# Sheet1.net
KiCad netlist of a schematic drawn in Altium Designer
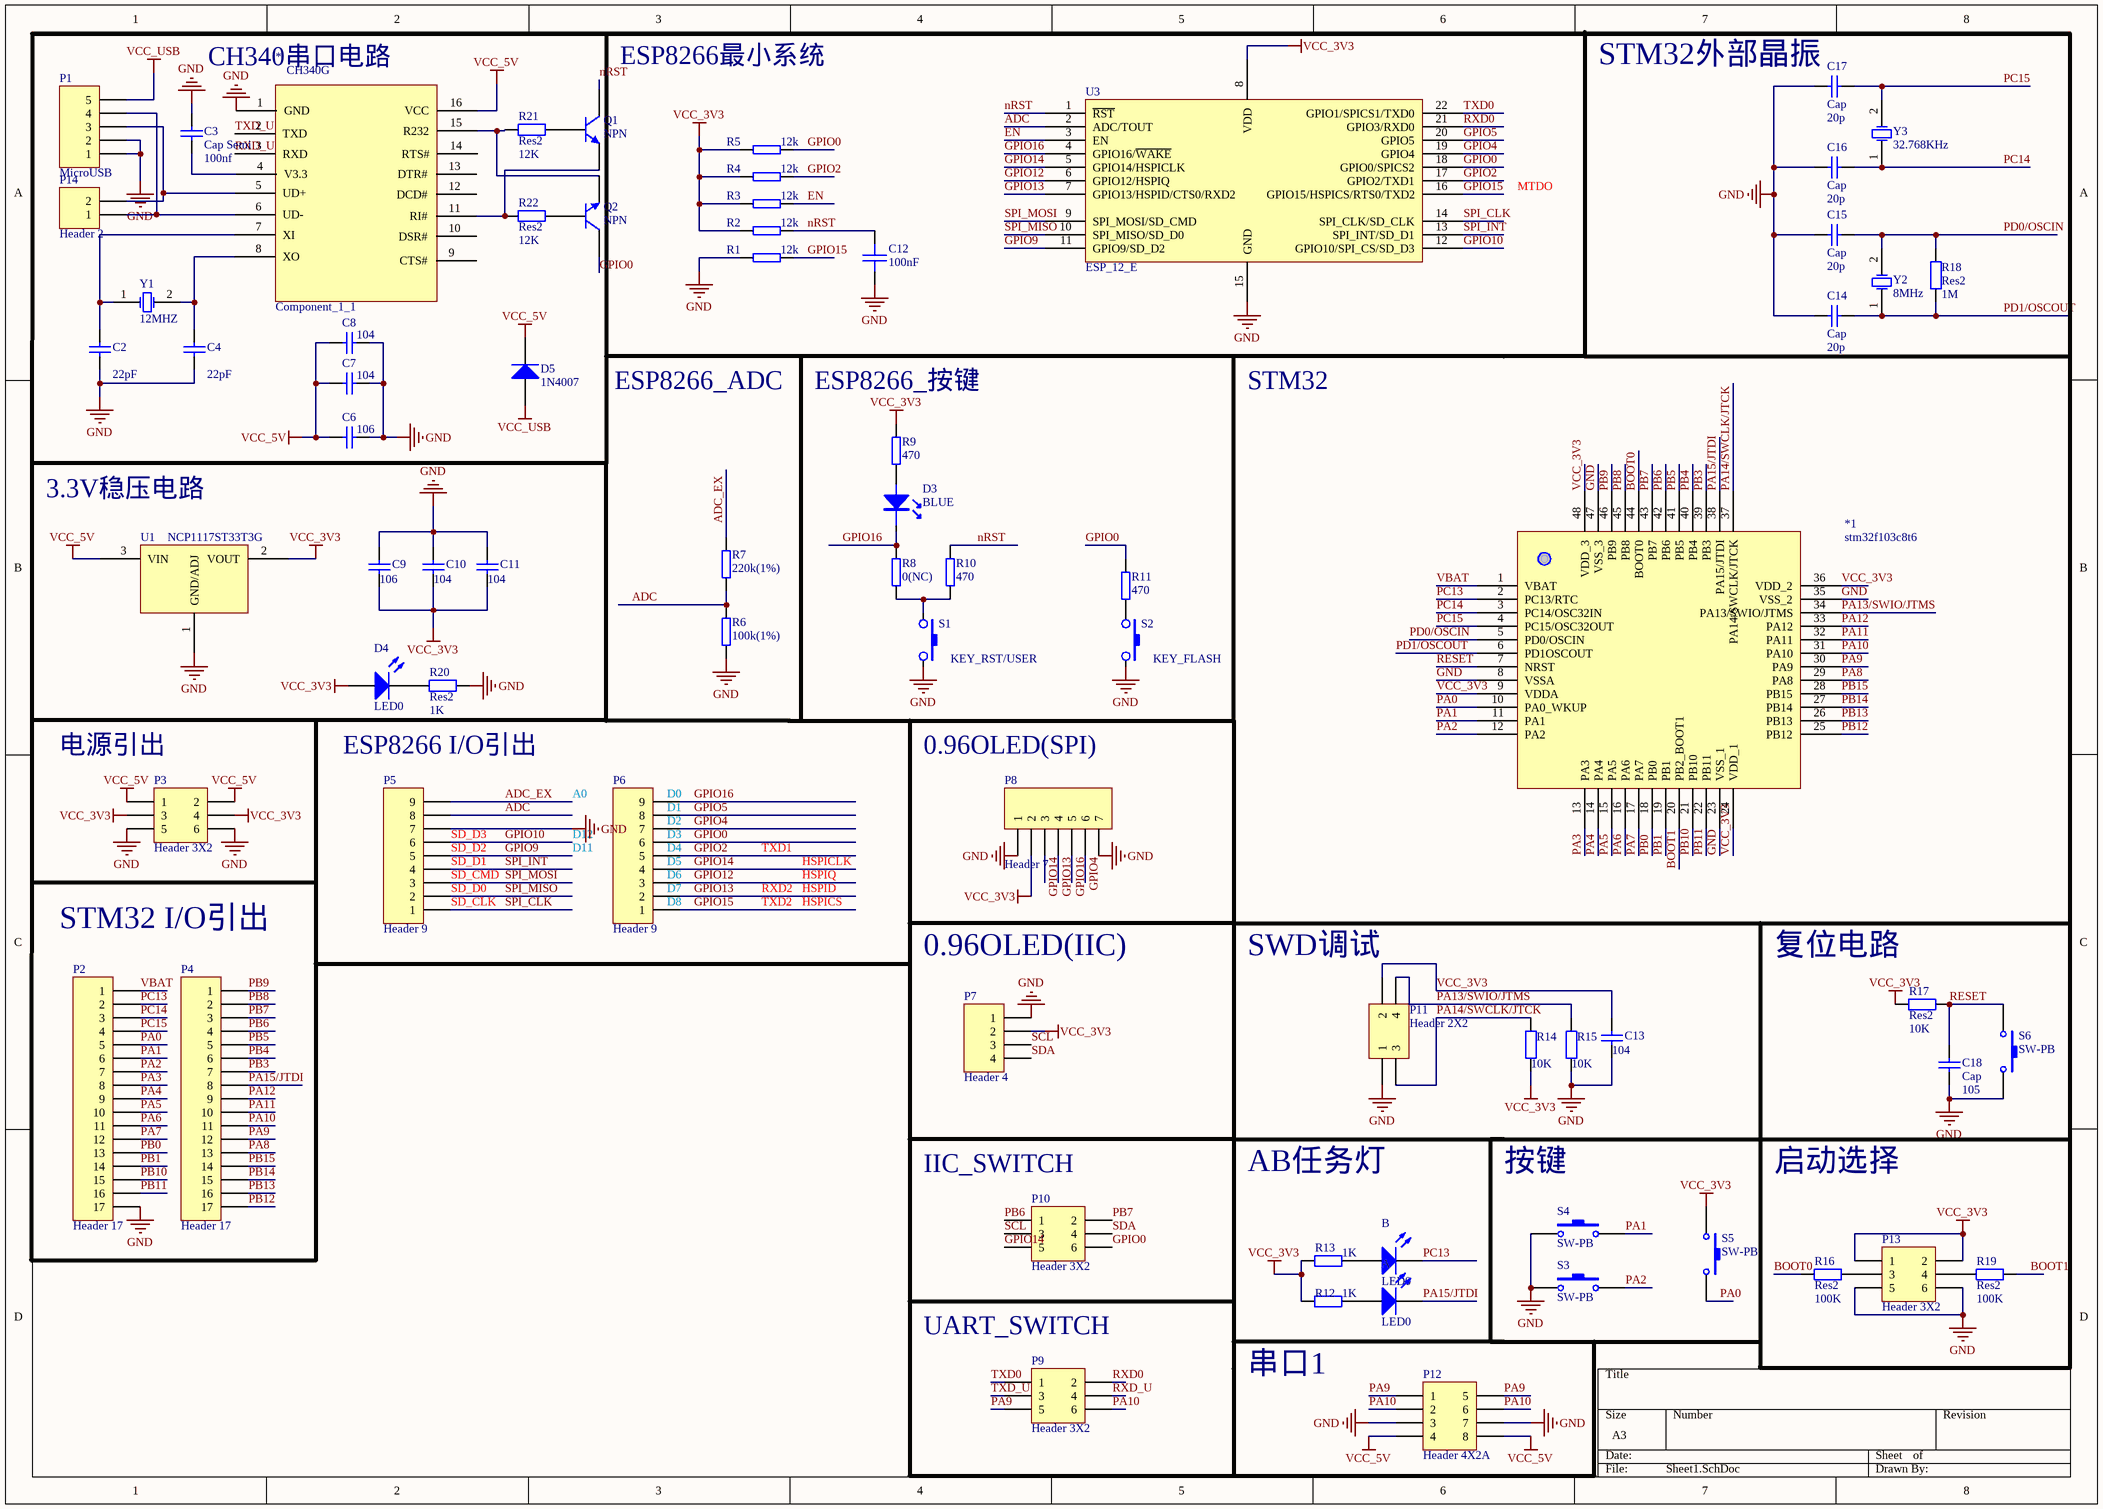
[diagram p0: Sheet1.SchDoc]

(export (version "E")
  (design (tool "Eeschema 10.0.6"))
  (components
    (comp (ref "*") (value "Component_1_1") (libsource (lib "CH340G") (part "Component_1_1")))
    (comp (ref "*1")
      (value "stm32f103c8t6")
      (footprint "LQFP-48_M")
      (libsource (lib "YL_Board") (part "stm32f103c8t6"))
    )
    (comp (ref "A")
      (value "LED0")
      (footprint "2012[0805]")
      (description "Typical INFRARED GaAs LED")
      (fields (field (name "PUBLISHER") "Altium Limited"))
      (libsource (lib "Miscellaneous Devices") (part "LED0"))
    )
    (comp (ref "B")
      (value "LED0")
      (footprint "2012[0805]")
      (description "Typical INFRARED GaAs LED")
      (fields (field (name "PUBLISHER") "Altium Limited"))
      (libsource (lib "Miscellaneous Devices") (part "LED0"))
    )
    (comp (ref "C2")
      (value "22pF")
      (footprint "2012[0805]")
      (description "Capacitor")
      (fields (field (name "Comment") "Cap") (field (name "PUBLISHER") "Altium Limited"))
      (libsource (lib "Miscellaneous Devices") (part "Cap"))
    )
    (comp (ref "C3")
      (value "Cap Semi")
      (footprint "2012[0805]")
      (description "Capacitor (Semiconductor SIM Model)")
      (fields (field (name "ALTIUM_VALUE") "100nf") (field (name "PUBLISHER") "Altium Limited"))
      (libsource (lib "Miscellaneous Devices") (part "Cap Semi"))
    )
    (comp (ref "C4")
      (value "22pF")
      (footprint "2012[0805]")
      (description "Capacitor")
      (fields (field (name "Comment") "Cap") (field (name "PUBLISHER") "Altium Limited"))
      (libsource (lib "Miscellaneous Devices") (part "Cap"))
    )
    (comp (ref "C6")
      (value "106")
      (footprint "C1206")
      (description "Capacitor (Semiconductor SIM Model)")
      (fields (field (name "Comment") "Cap Semi") (field (name "PUBLISHER") "Altium Limited"))
      (libsource (lib "Miscellaneous Devices") (part "Cap Semi"))
    )
    (comp (ref "C7")
      (value "104")
      (footprint "2012[0805]")
      (description "Capacitor (Semiconductor SIM Model)")
      (fields (field (name "Comment") "Cap Semi") (field (name "PUBLISHER") "Altium Limited"))
      (libsource (lib "Miscellaneous Devices") (part "Cap Semi"))
    )
    (comp (ref "C8")
      (value "104")
      (footprint "2012[0805]")
      (description "Capacitor (Semiconductor SIM Model)")
      (fields (field (name "Comment") "Cap Semi") (field (name "PUBLISHER") "Altium Limited"))
      (libsource (lib "Miscellaneous Devices") (part "Cap Semi"))
    )
    (comp (ref "C9")
      (value "106")
      (footprint "C1206")
      (description "Capacitor (Semiconductor SIM Model)")
      (fields (field (name "Comment") "Cap Semi") (field (name "PUBLISHER") "Altium Limited"))
      (libsource (lib "Miscellaneous Devices") (part "Cap Semi"))
    )
    (comp (ref "C10")
      (value "104")
      (footprint "2012[0805]")
      (description "Capacitor (Semiconductor SIM Model)")
      (fields (field (name "Comment") "Cap Semi") (field (name "PUBLISHER") "Altium Limited"))
      (libsource (lib "Miscellaneous Devices") (part "Cap Semi"))
    )
    (comp (ref "C11")
      (value "104")
      (footprint "2012[0805]")
      (description "Capacitor (Semiconductor SIM Model)")
      (fields (field (name "Comment") "Cap Semi") (field (name "PUBLISHER") "Altium Limited"))
      (libsource (lib "Miscellaneous Devices") (part "Cap Semi"))
    )
    (comp (ref "C12")
      (value "100nF")
      (footprint "2012[0805]")
      (description "Surface mount capacitor 0402")
      (libsource (lib "Vowstar_Basic_Device") (part "SMT_C_0402"))
    )
    (comp (ref "C13")
      (value "104")
      (footprint "2012[0805]")
      (description "Capacitor")
      (fields (field (name "Comment") "Cap") (field (name "PUBLISHER") "Altium Limited"))
      (libsource (lib "Miscellaneous Devices") (part "Cap"))
    )
    (comp (ref "C14")
      (value "Cap")
      (footprint "2012[0805]")
      (description "Capacitor")
      (fields (field (name "ALTIUM_VALUE") "20p") (field (name "PUBLISHER") "Altium Limited"))
      (libsource (lib "Miscellaneous Devices") (part "Cap"))
    )
    (comp (ref "C15")
      (value "Cap")
      (footprint "2012[0805]")
      (description "Capacitor")
      (fields (field (name "ALTIUM_VALUE") "20p") (field (name "PUBLISHER") "Altium Limited"))
      (libsource (lib "Miscellaneous Devices") (part "Cap"))
    )
    (comp (ref "C16")
      (value "Cap")
      (footprint "2012[0805]")
      (description "Capacitor")
      (fields (field (name "ALTIUM_VALUE") "20p") (field (name "PUBLISHER") "Altium Limited"))
      (libsource (lib "Miscellaneous Devices") (part "Cap"))
    )
    (comp (ref "C17")
      (value "Cap")
      (footprint "2012[0805]")
      (description "Capacitor")
      (fields (field (name "ALTIUM_VALUE") "20p") (field (name "PUBLISHER") "Altium Limited"))
      (libsource (lib "Miscellaneous Devices") (part "Cap"))
    )
    (comp (ref "C18")
      (value "Cap")
      (footprint "2012[0805]")
      (description "Capacitor")
      (fields (field (name "ALTIUM_VALUE") "105") (field (name "PUBLISHER") "Altium Limited"))
      (libsource (lib "Miscellaneous Devices") (part "Cap"))
    )
    (comp (ref "D3")
      (value "BLUE")
      (footprint "2012[0805]")
      (description "SMT LED")
      (libsource (lib "Vowstar_Basic_Device") (part "SMT_LED_0603"))
    )
    (comp (ref "D4")
      (value "LED0")
      (footprint "2012[0805]")
      (description "Typical INFRARED GaAs LED")
      (fields (field (name "PUBLISHER") "Altium Limited"))
      (libsource (lib "Miscellaneous Devices") (part "LED0"))
    )
    (comp (ref "D5")
      (value "1N4007")
      (footprint "2012[0805]")
      (description "1.0 Ampere General Purpose Rectifier")
      (fields (field (name "PUBLISHER") "Altium Limited"))
      (libsource (lib "FSC Discrete Rectifier") (part "1N4007"))
    )
    (comp (ref "P1")
      (value "MicroUSB")
      (footprint "Micro_USB")
      (description "Header, 5-Pin")
      (fields (field (name "PUBLISHER") "Altium Limited"))
      (libsource (lib "Miscellaneous Connectors") (part "Header 5"))
    )
    (comp (ref "P2")
      (value "Header 17")
      (footprint "HDR1X17")
      (description "Header, 17-Pin")
      (fields (field (name "PUBLISHER") "Altium Limited"))
      (libsource (lib "Miscellaneous Connectors") (part "Header 17"))
    )
    (comp (ref "P3")
      (value "Header 3X2")
      (footprint "HDR2X3")
      (description "Header, 3-Pin, Dual row")
      (fields (field (name "PUBLISHER") "Altium Limited"))
      (libsource (lib "Miscellaneous Connectors") (part "Header 3X2"))
    )
    (comp (ref "P4")
      (value "Header 17")
      (footprint "HDR1X17")
      (description "Header, 17-Pin")
      (fields (field (name "PUBLISHER") "Altium Limited"))
      (libsource (lib "Miscellaneous Connectors") (part "Header 17"))
    )
    (comp (ref "P5")
      (value "Header 9")
      (footprint "HDR1X9")
      (description "Header, 9-Pin")
      (fields (field (name "PUBLISHER") "Altium Limited"))
      (libsource (lib "Miscellaneous Connectors") (part "Header 9"))
    )
    (comp (ref "P6")
      (value "Header 9")
      (footprint "HDR1X9")
      (description "Header, 9-Pin")
      (fields (field (name "PUBLISHER") "Altium Limited"))
      (libsource (lib "Miscellaneous Connectors") (part "Header 9"))
    )
    (comp (ref "P7")
      (value "Header 4")
      (footprint "HDR1X4")
      (description "Header, 4-Pin")
      (fields (field (name "PUBLISHER") "Altium Limited"))
      (libsource (lib "Miscellaneous Connectors") (part "Header 4"))
    )
    (comp (ref "P8")
      (value "Header 7")
      (footprint "HDR1X7")
      (description "Header, 7-Pin")
      (fields (field (name "PUBLISHER") "Altium Limited"))
      (libsource (lib "Miscellaneous Connectors") (part "Header 7"))
    )
    (comp (ref "P9")
      (value "Header 3X2")
      (footprint "HDR2X3")
      (description "Header, 3-Pin, Dual row")
      (fields (field (name "PUBLISHER") "Altium Limited"))
      (libsource (lib "Miscellaneous Connectors") (part "Header 3X2"))
    )
    (comp (ref "P10")
      (value "Header 3X2")
      (footprint "HDR2X3")
      (description "Header, 3-Pin, Dual row")
      (fields (field (name "PUBLISHER") "Altium Limited"))
      (libsource (lib "Miscellaneous Connectors") (part "Header 3X2"))
    )
    (comp (ref "P11")
      (value "Header 2X2")
      (footprint "HDR2X2")
      (description "Header, 2-Pin, Dual row")
      (fields (field (name "PUBLISHER") "Altium Limited"))
      (libsource (lib "Miscellaneous Connectors") (part "Header 2X2"))
    )
    (comp (ref "P12")
      (value "Header 4X2A")
      (footprint "HDR2X4_CEN")
      (description "Header, 4-Pin, Dual row")
      (fields (field (name "PUBLISHER") "Altium Limited"))
      (libsource (lib "Miscellaneous Connectors") (part "Header 4X2A"))
    )
    (comp (ref "P13")
      (value "Header 3X2")
      (footprint "HDR2X3")
      (description "Header, 3-Pin, Dual row")
      (fields (field (name "PUBLISHER") "Altium Limited"))
      (libsource (lib "Miscellaneous Connectors") (part "Header 3X2"))
    )
    (comp (ref "P14")
      (value "Header 2")
      (footprint "HDR1X2")
      (description "Header, 2-Pin")
      (fields (field (name "PUBLISHER") "Altium Limited"))
      (libsource (lib "Miscellaneous Connectors") (part "Header 2"))
    )
    (comp (ref "Q1")
      (value "NPN")
      (footprint "SC70-LB3_L")
      (description "NPN Bipolar Transistor")
      (fields (field (name "PUBLISHER") "Altium Limited"))
      (libsource (lib "Miscellaneous Devices") (part "NPN"))
    )
    (comp (ref "Q2")
      (value "NPN")
      (footprint "SC70-LB3_L")
      (description "NPN Bipolar Transistor")
      (fields (field (name "PUBLISHER") "Altium Limited"))
      (libsource (lib "Miscellaneous Devices") (part "NPN"))
    )
    (comp (ref "R1")
      (value "12k")
      (footprint "2012[0805]")
      (description "Surface mount resistor 0402")
      (libsource (lib "Vowstar_Basic_Device") (part "SMT_R_0402"))
    )
    (comp (ref "R2")
      (value "12k")
      (footprint "2012[0805]")
      (description "Surface mount resistor 0402")
      (libsource (lib "Vowstar_Basic_Device") (part "SMT_R_0402"))
    )
    (comp (ref "R3")
      (value "12k")
      (footprint "2012[0805]")
      (description "Surface mount resistor 0402")
      (libsource (lib "Vowstar_Basic_Device") (part "SMT_R_0402"))
    )
    (comp (ref "R4")
      (value "12k")
      (footprint "2012[0805]")
      (description "Surface mount resistor 0402")
      (libsource (lib "Vowstar_Basic_Device") (part "SMT_R_0402"))
    )
    (comp (ref "R5")
      (value "12k")
      (footprint "2012[0805]")
      (description "Surface mount resistor 0402")
      (libsource (lib "Vowstar_Basic_Device") (part "SMT_R_0402"))
    )
    (comp (ref "R6")
      (value "100k(1%)")
      (footprint "2012[0805]")
      (description "Surface mount resistor 0402")
      (libsource (lib "Vowstar_Basic_Device") (part "SMT_R_0402"))
    )
    (comp (ref "R7")
      (value "220k(1%)")
      (footprint "2012[0805]")
      (description "Surface mount resistor 0402")
      (libsource (lib "Vowstar_Basic_Device") (part "SMT_R_0402"))
    )
    (comp (ref "R8")
      (value "0(NC)")
      (footprint "2012[0805]")
      (description "Surface mount resistor 0402")
      (libsource (lib "Vowstar_Basic_Device") (part "SMT_R_0402"))
    )
    (comp (ref "R9")
      (value "470")
      (footprint "2012[0805]")
      (description "Surface mount resistor 0402")
      (libsource (lib "Vowstar_Basic_Device") (part "SMT_R_0402"))
    )
    (comp (ref "R10")
      (value "470")
      (footprint "2012[0805]")
      (description "Surface mount resistor 0402")
      (libsource (lib "Vowstar_Basic_Device") (part "SMT_R_0402"))
    )
    (comp (ref "R11")
      (value "470")
      (footprint "2012[0805]")
      (description "Surface mount resistor 0402")
      (libsource (lib "Vowstar_Basic_Device") (part "SMT_R_0402"))
    )
    (comp (ref "R12")
      (value "1K")
      (footprint "2012[0805]")
      (description "Resistor")
      (fields (field (name "Comment") "Res2") (field (name "PUBLISHER") "Altium Limited"))
      (libsource (lib "Miscellaneous Devices") (part "Res2"))
    )
    (comp (ref "R13")
      (value "1K")
      (footprint "2012[0805]")
      (description "Resistor")
      (fields (field (name "Comment") "Res2") (field (name "PUBLISHER") "Altium Limited"))
      (libsource (lib "Miscellaneous Devices") (part "Res2"))
    )
    (comp (ref "R14")
      (value "10K")
      (footprint "2012[0805]")
      (description "Resistor")
      (fields (field (name "Comment") "Res2") (field (name "PUBLISHER") "Altium Limited"))
      (libsource (lib "") (part "Res2_1"))
    )
    (comp (ref "R15")
      (value "10K")
      (footprint "2012[0805]")
      (description "Resistor")
      (fields (field (name "Comment") "Res2") (field (name "PUBLISHER") "Altium Limited"))
      (libsource (lib "") (part "Res2_1"))
    )
    (comp (ref "R16")
      (value "Res2")
      (footprint "2012[0805]")
      (description "Resistor")
      (fields (field (name "ALTIUM_VALUE") "100K") (field (name "PUBLISHER") "Altium Limited"))
      (libsource (lib "Miscellaneous Devices") (part "Res2"))
    )
    (comp (ref "R17")
      (value "Res2")
      (footprint "2012[0805]")
      (description "Resistor")
      (fields (field (name "ALTIUM_VALUE") "10K") (field (name "PUBLISHER") "Altium Limited"))
      (libsource (lib "Miscellaneous Devices") (part "Res2"))
    )
    (comp (ref "R18")
      (value "Res2")
      (footprint "2012[0805]")
      (description "Resistor")
      (fields (field (name "ALTIUM_VALUE") "1M") (field (name "PUBLISHER") "Altium Limited"))
      (libsource (lib "") (part "Res2_1"))
    )
    (comp (ref "R19")
      (value "Res2")
      (footprint "2012[0805]")
      (description "Resistor")
      (fields (field (name "ALTIUM_VALUE") "100K") (field (name "PUBLISHER") "Altium Limited"))
      (libsource (lib "Miscellaneous Devices") (part "Res2"))
    )
    (comp (ref "R20")
      (value "Res2")
      (footprint "2012[0805]")
      (description "Resistor")
      (fields (field (name "ALTIUM_VALUE") "1K") (field (name "PUBLISHER") "Altium Limited"))
      (libsource (lib "Miscellaneous Devices") (part "Res2"))
    )
    (comp (ref "R21")
      (value "Res2")
      (footprint "2012[0805]")
      (description "Resistor")
      (fields (field (name "ALTIUM_VALUE") "12K") (field (name "PUBLISHER") "Altium Limited"))
      (libsource (lib "Miscellaneous Devices") (part "Res2"))
    )
    (comp (ref "R22")
      (value "Res2")
      (footprint "2012[0805]")
      (description "Resistor")
      (fields (field (name "ALTIUM_VALUE") "12K") (field (name "PUBLISHER") "Altium Limited"))
      (libsource (lib "Miscellaneous Devices") (part "Res2"))
    )
    (comp (ref "S1")
      (value "KEY_RST/USER")
      (footprint "KEY")
      (description "SMT Tactile ?Switch PTS 820 Series")
      (libsource (lib "Vowstar_Switch") (part "SMT_SW_PTS_820"))
    )
    (comp (ref "S2")
      (value "KEY_FLASH")
      (footprint "KEY")
      (description "SMT Tactile ?Switch PTS 820 Series")
      (libsource (lib "Vowstar_Switch") (part "SMT_SW_PTS_820"))
    )
    (comp (ref "S3")
      (value "SW-PB")
      (footprint "KEY")
      (description "Switch")
      (fields (field (name "PUBLISHER") "Altium Limited"))
      (libsource (lib "Miscellaneous Devices") (part "SW-PB"))
    )
    (comp (ref "S4")
      (value "SW-PB")
      (footprint "KEY")
      (description "Switch")
      (fields (field (name "PUBLISHER") "Altium Limited"))
      (libsource (lib "Miscellaneous Devices") (part "SW-PB"))
    )
    (comp (ref "S5")
      (value "SW-PB")
      (footprint "KEY")
      (description "Switch")
      (fields (field (name "PUBLISHER") "Altium Limited"))
      (libsource (lib "Miscellaneous Devices") (part "SW-PB"))
    )
    (comp (ref "S6")
      (value "SW-PB")
      (footprint "KEY")
      (description "Switch")
      (fields (field (name "PUBLISHER") "Altium Limited"))
      (libsource (lib "Miscellaneous Devices") (part "SW-PB"))
    )
    (comp (ref "U1")
      (value "NCP1117ST33T3G")
      (footprint "SOT-223")
      (description "NCP1117, NCV1117. 1.0 A Low-Dropout Positive  Fixed and Adjustable  Voltage Regulators")
      (libsource (lib "Vowstar_IC_General") (part "NCP1117"))
    )
    (comp (ref "U3")
      (value "ESP_12_E")
      (footprint "ESP_12F")
      (description "ESP-12 Wi-Fi Module by AI-Thinker")
      (libsource (lib "Vowstar_Module") (part "ESP_12_E"))
    )
    (comp (ref "Y1")
      (value "12MHZ")
      (footprint "XTAL-HCM49")
      (description "Crystal Oscillator")
      (fields (field (name "PUBLISHER") "Altium Limited"))
      (libsource (lib "Miscellaneous Devices") (part "XTAL"))
    )
    (comp (ref "Y2")
      (value "8MHz")
      (footprint "XTAL-HCM49")
      (description "Crystal Oscillator")
      (fields (field (name "PUBLISHER") "Altium Limited"))
      (libsource (lib "Miscellaneous Devices") (part "XTAL"))
    )
    (comp (ref "Y3")
      (value "32.768KHz")
      (footprint "XTAL32-2")
      (description "Crystal Oscillator")
      (fields (field (name "PUBLISHER") "Altium Limited"))
      (libsource (lib "Miscellaneous Devices") (part "XTAL"))
    )
  )
  (nets
    (net (code "1") (name "/ADC") (class "Default")
      (node (ref "P5") (pin "8") (pinfunction "8_8") (pintype "passive"))
      (node (ref "R6") (pin "2") (pinfunction "2_2") (pintype "passive"))
      (node (ref "R7") (pin "1") (pinfunction "1_1") (pintype "passive"))
      (node (ref "U3") (pin "2") (pinfunction "ADC/TOUT_2") (pintype "passive"))
    )
    (net (code "2") (name "/ADC_EX") (class "Default")
      (node (ref "P5") (pin "9") (pinfunction "9_9") (pintype "passive"))
      (node (ref "R7") (pin "2") (pinfunction "2_2") (pintype "passive"))
    )
    (net (code "3") (name "/BOOT0") (class "Default")
      (node (ref "*1") (pin "44") (pinfunction "BOOT0_44") (pintype "passive"))
      (node (ref "R16") (pin "1") (pinfunction "1_1") (pintype "passive"))
    )
    (net (code "4") (name "/BOOT1") (class "Default")
      (node (ref "*1") (pin "20") (pinfunction "PB2_BOOT1_20") (pintype "passive"))
      (node (ref "R19") (pin "2") (pinfunction "2_2") (pintype "passive"))
    )
    (net (code "5") (name "/EN") (class "Default")
      (node (ref "R3") (pin "2") (pinfunction "2_2") (pintype "passive"))
      (node (ref "U3") (pin "3") (pinfunction "EN_3") (pintype "passive"))
    )
    (net (code "6") (name "/GPIO0") (class "Default")
      (node (ref "P10") (pin "6") (pinfunction "6_6") (pintype "passive"))
      (node (ref "P6") (pin "6") (pinfunction "6_6") (pintype "passive"))
      (node (ref "Q2") (pin "1") (pinfunction "C_1") (pintype "passive"))
      (node (ref "R11") (pin "2") (pinfunction "2_2") (pintype "passive"))
      (node (ref "R5") (pin "2") (pinfunction "2_2") (pintype "passive"))
      (node (ref "U3") (pin "18") (pinfunction "GPIO0/SPICS2_18") (pintype "passive"))
    )
    (net (code "7") (name "/GPIO2") (class "Default")
      (node (ref "P6") (pin "5") (pinfunction "5_5") (pintype "passive"))
      (node (ref "R4") (pin "2") (pinfunction "2_2") (pintype "passive"))
      (node (ref "U3") (pin "17") (pinfunction "GPIO2/TXD1_17") (pintype "passive"))
    )
    (net (code "8") (name "/GPIO4") (class "Default")
      (node (ref "P6") (pin "7") (pinfunction "7_7") (pintype "passive"))
      (node (ref "P8") (pin "6") (pinfunction "6_6") (pintype "passive"))
      (node (ref "U3") (pin "19") (pinfunction "GPIO4_19") (pintype "passive"))
    )
    (net (code "9") (name "/GPIO5") (class "Default")
      (node (ref "P6") (pin "8") (pinfunction "8_8") (pintype "passive"))
      (node (ref "U3") (pin "20") (pinfunction "GPIO5_20") (pintype "passive"))
    )
    (net (code "10") (name "/GPIO9") (class "Default")
      (node (ref "P5") (pin "5") (pinfunction "5_5") (pintype "passive"))
      (node (ref "U3") (pin "11") (pinfunction "GPIO9/SD_D2_11") (pintype "passive"))
    )
    (net (code "11") (name "/GPIO10") (class "Default")
      (node (ref "P5") (pin "6") (pinfunction "6_6") (pintype "passive"))
      (node (ref "U3") (pin "12") (pinfunction "GPIO10/SPI_CS/SD_D3_12") (pintype "passive"))
    )
    (net (code "12") (name "/GPIO12") (class "Default")
      (node (ref "P6") (pin "3") (pinfunction "3_3") (pintype "passive"))
      (node (ref "U3") (pin "6") (pinfunction "GPIO12/HSPIQ_6") (pintype "passive"))
    )
    (net (code "13") (name "/GPIO13") (class "Default")
      (node (ref "P6") (pin "2") (pinfunction "2_2") (pintype "passive"))
      (node (ref "P8") (pin "4") (pinfunction "4_4") (pintype "passive"))
      (node (ref "U3") (pin "7") (pinfunction "GPIO13/HSPID/CTS0/RXD2_7") (pintype "passive"))
    )
    (net (code "14") (name "/GPIO14") (class "Default")
      (node (ref "P10") (pin "5") (pinfunction "5_5") (pintype "passive"))
      (node (ref "P6") (pin "4") (pinfunction "4_4") (pintype "passive"))
      (node (ref "P8") (pin "3") (pinfunction "3_3") (pintype "passive"))
      (node (ref "U3") (pin "5") (pinfunction "GPIO14/HSPICLK_5") (pintype "passive"))
    )
    (net (code "15") (name "/GPIO15") (class "Default")
      (node (ref "P6") (pin "1") (pinfunction "1_1") (pintype "passive"))
      (node (ref "R1") (pin "2") (pinfunction "2_2") (pintype "passive"))
      (node (ref "U3") (pin "16") (pinfunction "GPIO15/HSPICS/RTS0/TXD2_16") (pintype "passive"))
    )
    (net (code "16") (name "/GPIO16") (class "Default")
      (node (ref "D3") (pin "2") (pinfunction "K_2") (pintype "passive"))
      (node (ref "P6") (pin "9") (pinfunction "9_9") (pintype "passive"))
      (node (ref "P8") (pin "5") (pinfunction "5_5") (pintype "passive"))
      (node (ref "R8") (pin "2") (pinfunction "2_2") (pintype "passive"))
      (node (ref "U3") (pin "4") (pinfunction "GPIO16/~{WAKE}_4") (pintype "passive"))
    )
    (net (code "17") (name "/PA0") (class "Default")
      (node (ref "*1") (pin "10") (pinfunction "PA0_WKUP_10") (pintype "passive"))
      (node (ref "P2") (pin "5") (pinfunction "5_5") (pintype "passive"))
      (node (ref "S5") (pin "2") (pinfunction "2_2") (pintype "passive"))
    )
    (net (code "18") (name "/PA1") (class "Default")
      (node (ref "*1") (pin "11") (pinfunction "PA1_11") (pintype "passive"))
      (node (ref "P2") (pin "6") (pinfunction "6_6") (pintype "passive"))
      (node (ref "S4") (pin "2") (pinfunction "2_2") (pintype "passive"))
    )
    (net (code "19") (name "/PA2") (class "Default")
      (node (ref "*1") (pin "12") (pinfunction "PA2_12") (pintype "passive"))
      (node (ref "P2") (pin "7") (pinfunction "7_7") (pintype "passive"))
      (node (ref "S3") (pin "2") (pinfunction "2_2") (pintype "passive"))
    )
    (net (code "20") (name "/PA3") (class "Default")
      (node (ref "*1") (pin "13") (pinfunction "PA3_13") (pintype "passive"))
      (node (ref "P2") (pin "8") (pinfunction "8_8") (pintype "passive"))
    )
    (net (code "21") (name "/PA4") (class "Default")
      (node (ref "*1") (pin "14") (pinfunction "PA4_14") (pintype "passive"))
      (node (ref "P2") (pin "9") (pinfunction "9_9") (pintype "passive"))
    )
    (net (code "22") (name "/PA5") (class "Default")
      (node (ref "*1") (pin "15") (pinfunction "PA5_15") (pintype "passive"))
      (node (ref "P2") (pin "10") (pinfunction "10_10") (pintype "passive"))
    )
    (net (code "23") (name "/PA6") (class "Default")
      (node (ref "*1") (pin "16") (pinfunction "PA6_16") (pintype "passive"))
      (node (ref "P2") (pin "11") (pinfunction "11_11") (pintype "passive"))
    )
    (net (code "24") (name "/PA7") (class "Default")
      (node (ref "*1") (pin "17") (pinfunction "PA7_17") (pintype "passive"))
      (node (ref "P2") (pin "12") (pinfunction "12_12") (pintype "passive"))
    )
    (net (code "25") (name "/PA8") (class "Default")
      (node (ref "*1") (pin "29") (pinfunction "PA8_29") (pintype "passive"))
      (node (ref "P4") (pin "13") (pinfunction "13_13") (pintype "passive"))
    )
    (net (code "26") (name "/PA9") (class "Default")
      (node (ref "*1") (pin "30") (pinfunction "PA9_30") (pintype "passive"))
      (node (ref "P12") (pin "1") (pinfunction "1_1") (pintype "passive"))
      (node (ref "P12") (pin "5") (pinfunction "5_5") (pintype "passive"))
      (node (ref "P4") (pin "12") (pinfunction "12_12") (pintype "passive"))
      (node (ref "P9") (pin "5") (pinfunction "5_5") (pintype "passive"))
    )
    (net (code "27") (name "/PA10") (class "Default")
      (node (ref "*1") (pin "31") (pinfunction "PA10_31") (pintype "passive"))
      (node (ref "P12") (pin "2") (pinfunction "2_2") (pintype "passive"))
      (node (ref "P12") (pin "6") (pinfunction "6_6") (pintype "passive"))
      (node (ref "P4") (pin "11") (pinfunction "11_11") (pintype "passive"))
      (node (ref "P9") (pin "6") (pinfunction "6_6") (pintype "passive"))
    )
    (net (code "28") (name "/PA11") (class "Default")
      (node (ref "*1") (pin "32") (pinfunction "PA11_32") (pintype "passive"))
      (node (ref "P4") (pin "10") (pinfunction "10_10") (pintype "passive"))
    )
    (net (code "29") (name "/PA12") (class "Default")
      (node (ref "*1") (pin "33") (pinfunction "PA12_33") (pintype "passive"))
      (node (ref "P4") (pin "9") (pinfunction "9_9") (pintype "passive"))
    )
    (net (code "30") (name "/PA13{slash}SWIO{slash}JTMS") (class "Default")
      (node (ref "*1") (pin "34") (pinfunction "PA13/SWIO/JTMS_34") (pintype "passive"))
      (node (ref "P11") (pin "4") (pinfunction "4_4") (pintype "passive"))
      (node (ref "R15") (pin "2") (pinfunction "2_2") (pintype "passive"))
    )
    (net (code "31") (name "/PA14{slash}SWCLK{slash}JTCK") (class "Default")
      (node (ref "*1") (pin "37") (pinfunction "PA14/SWCLK/JTCK_37") (pintype "passive"))
      (node (ref "P11") (pin "3") (pinfunction "3_3") (pintype "passive"))
      (node (ref "R14") (pin "2") (pinfunction "2_2") (pintype "passive"))
    )
    (net (code "32") (name "/PA15{slash}JTDI") (class "Default")
      (node (ref "*1") (pin "38") (pinfunction "PA15/JTDI_38") (pintype "passive"))
      (node (ref "A") (pin "2") (pinfunction "K_2") (pintype "passive"))
      (node (ref "P4") (pin "8") (pinfunction "8_8") (pintype "passive"))
    )
    (net (code "33") (name "/PB0") (class "Default")
      (node (ref "*1") (pin "18") (pinfunction "PB0_18") (pintype "passive"))
      (node (ref "P2") (pin "13") (pinfunction "13_13") (pintype "passive"))
    )
    (net (code "34") (name "/PB1") (class "Default")
      (node (ref "*1") (pin "19") (pinfunction "PB1_19") (pintype "passive"))
      (node (ref "P2") (pin "14") (pinfunction "14_14") (pintype "passive"))
    )
    (net (code "35") (name "/PB3") (class "Default")
      (node (ref "*1") (pin "39") (pinfunction "PB3_39") (pintype "passive"))
      (node (ref "P4") (pin "7") (pinfunction "7_7") (pintype "passive"))
    )
    (net (code "36") (name "/PB4") (class "Default")
      (node (ref "*1") (pin "40") (pinfunction "PB4_40") (pintype "passive"))
      (node (ref "P4") (pin "6") (pinfunction "6_6") (pintype "passive"))
    )
    (net (code "37") (name "/PB5") (class "Default")
      (node (ref "*1") (pin "41") (pinfunction "PB5_41") (pintype "passive"))
      (node (ref "P4") (pin "5") (pinfunction "5_5") (pintype "passive"))
    )
    (net (code "38") (name "/PB6") (class "Default")
      (node (ref "*1") (pin "42") (pinfunction "PB6_42") (pintype "passive"))
      (node (ref "P10") (pin "1") (pinfunction "1_1") (pintype "passive"))
      (node (ref "P4") (pin "4") (pinfunction "4_4") (pintype "passive"))
    )
    (net (code "39") (name "/PB7") (class "Default")
      (node (ref "*1") (pin "43") (pinfunction "PB7_43") (pintype "passive"))
      (node (ref "P10") (pin "2") (pinfunction "2_2") (pintype "passive"))
      (node (ref "P4") (pin "3") (pinfunction "3_3") (pintype "passive"))
    )
    (net (code "40") (name "/PB8") (class "Default")
      (node (ref "*1") (pin "45") (pinfunction "PB8_45") (pintype "passive"))
      (node (ref "P4") (pin "2") (pinfunction "2_2") (pintype "passive"))
    )
    (net (code "41") (name "/PB9") (class "Default")
      (node (ref "*1") (pin "46") (pinfunction "PB9_46") (pintype "passive"))
      (node (ref "P4") (pin "1") (pinfunction "1_1") (pintype "passive"))
    )
    (net (code "42") (name "/PB10") (class "Default")
      (node (ref "*1") (pin "21") (pinfunction "PB10_21") (pintype "passive"))
      (node (ref "P2") (pin "15") (pinfunction "15_15") (pintype "passive"))
    )
    (net (code "43") (name "/PB11") (class "Default")
      (node (ref "*1") (pin "22") (pinfunction "PB11_22") (pintype "passive"))
      (node (ref "P2") (pin "16") (pinfunction "16_16") (pintype "passive"))
    )
    (net (code "44") (name "/PB12") (class "Default")
      (node (ref "*1") (pin "25") (pinfunction "PB12_25") (pintype "passive"))
      (node (ref "P4") (pin "17") (pinfunction "17_17") (pintype "passive"))
    )
    (net (code "45") (name "/PB13") (class "Default")
      (node (ref "*1") (pin "26") (pinfunction "PB13_26") (pintype "passive"))
      (node (ref "P4") (pin "16") (pinfunction "16_16") (pintype "passive"))
    )
    (net (code "46") (name "/PB14") (class "Default")
      (node (ref "*1") (pin "27") (pinfunction "PB14_27") (pintype "passive"))
      (node (ref "P4") (pin "15") (pinfunction "15_15") (pintype "passive"))
    )
    (net (code "47") (name "/PB15") (class "Default")
      (node (ref "*1") (pin "28") (pinfunction "PB15_28") (pintype "passive"))
      (node (ref "P4") (pin "14") (pinfunction "14_14") (pintype "passive"))
    )
    (net (code "48") (name "/PC13") (class "Default")
      (node (ref "*1") (pin "2") (pinfunction "PC13/RTC_2") (pintype "passive"))
      (node (ref "B") (pin "2") (pinfunction "K_2") (pintype "passive"))
      (node (ref "P2") (pin "2") (pinfunction "2_2") (pintype "passive"))
    )
    (net (code "49") (name "/PC14") (class "Default")
      (node (ref "*1") (pin "3") (pinfunction "PC14/OSC32IN_3") (pintype "passive"))
      (node (ref "C16") (pin "2") (pinfunction "2_2") (pintype "passive"))
      (node (ref "P2") (pin "3") (pinfunction "3_3") (pintype "passive"))
      (node (ref "Y3") (pin "1") (pinfunction "OSC1_1") (pintype "passive"))
    )
    (net (code "50") (name "/PC15") (class "Default")
      (node (ref "*1") (pin "4") (pinfunction "PC15/OSC32OUT_4") (pintype "passive"))
      (node (ref "C17") (pin "2") (pinfunction "2_2") (pintype "passive"))
      (node (ref "P2") (pin "4") (pinfunction "4_4") (pintype "passive"))
      (node (ref "Y3") (pin "2") (pinfunction "OSC2_2") (pintype "passive"))
    )
    (net (code "51") (name "/PD0{slash}OSCIN") (class "Default")
      (node (ref "*1") (pin "5") (pinfunction "PD0/OSCIN_5") (pintype "passive"))
      (node (ref "C15") (pin "2") (pinfunction "2_2") (pintype "passive"))
      (node (ref "R18") (pin "2") (pinfunction "2_2") (pintype "passive"))
      (node (ref "Y2") (pin "2") (pinfunction "OSC2_2") (pintype "passive"))
    )
    (net (code "52") (name "/PD1{slash}OSCOUT") (class "Default")
      (node (ref "*1") (pin "6") (pinfunction "PD1OSCOUT_6") (pintype "passive"))
      (node (ref "C14") (pin "2") (pinfunction "2_2") (pintype "passive"))
      (node (ref "R18") (pin "1") (pinfunction "1_1") (pintype "passive"))
      (node (ref "Y2") (pin "1") (pinfunction "OSC1_1") (pintype "passive"))
    )
    (net (code "53") (name "/RESET") (class "Default")
      (node (ref "*1") (pin "7") (pinfunction "NRST_7") (pintype "passive"))
      (node (ref "C18") (pin "2") (pinfunction "2_2") (pintype "passive"))
      (node (ref "R17") (pin "2") (pinfunction "2_2") (pintype "passive"))
      (node (ref "S6") (pin "1") (pinfunction "1_1") (pintype "passive"))
    )
    (net (code "54") (name "/RXD0") (class "Default")
      (node (ref "P9") (pin "2") (pinfunction "2_2") (pintype "passive"))
      (node (ref "U3") (pin "21") (pinfunction "GPIO3/RXD0_21") (pintype "passive"))
    )
    (net (code "55") (name "/RXD_U") (class "Default")
      (node (ref "*") (pin "3") (pinfunction "RXD_3") (pintype "passive"))
      (node (ref "P9") (pin "4") (pinfunction "4_4") (pintype "passive"))
    )
    (net (code "56") (name "/SCL") (class "Default")
      (node (ref "P10") (pin "3") (pinfunction "3_3") (pintype "passive"))
      (node (ref "P7") (pin "3") (pinfunction "3_3") (pintype "passive"))
    )
    (net (code "57") (name "/SDA") (class "Default")
      (node (ref "P10") (pin "4") (pinfunction "4_4") (pintype "passive"))
      (node (ref "P7") (pin "4") (pinfunction "4_4") (pintype "passive"))
    )
    (net (code "58") (name "/SPI_CLK") (class "Default")
      (node (ref "P5") (pin "1") (pinfunction "1_1") (pintype "passive"))
      (node (ref "U3") (pin "14") (pinfunction "SPI_CLK/SD_CLK_14") (pintype "passive"))
    )
    (net (code "59") (name "/SPI_INT") (class "Default")
      (node (ref "P5") (pin "4") (pinfunction "4_4") (pintype "passive"))
      (node (ref "U3") (pin "13") (pinfunction "SPI_INT/SD_D1_13") (pintype "passive"))
    )
    (net (code "60") (name "/SPI_MISO") (class "Default")
      (node (ref "P5") (pin "2") (pinfunction "2_2") (pintype "passive"))
      (node (ref "U3") (pin "10") (pinfunction "SPI_MISO/SD_D0_10") (pintype "passive"))
    )
    (net (code "61") (name "/SPI_MOSI") (class "Default")
      (node (ref "P5") (pin "3") (pinfunction "3_3") (pintype "passive"))
      (node (ref "U3") (pin "9") (pinfunction "SPI_MOSI/SD_CMD_9") (pintype "passive"))
    )
    (net (code "62") (name "/TXD0") (class "Default")
      (node (ref "P9") (pin "1") (pinfunction "1_1") (pintype "passive"))
      (node (ref "U3") (pin "22") (pinfunction "GPIO1/SPICS1/TXD0_22") (pintype "passive"))
    )
    (net (code "63") (name "/TXD_U") (class "Default")
      (node (ref "*") (pin "2") (pinfunction "TXD_2") (pintype "passive"))
      (node (ref "P9") (pin "3") (pinfunction "3_3") (pintype "passive"))
    )
    (net (code "64") (name "/VBAT") (class "Default")
      (node (ref "*1") (pin "1") (pinfunction "VBAT_1") (pintype "passive"))
      (node (ref "P2") (pin "1") (pinfunction "1_1") (pintype "passive"))
    )
    (net (code "65") (name "/nRST") (class "Default")
      (node (ref "C12") (pin "1") (pinfunction "1_1") (pintype "passive"))
      (node (ref "Q1") (pin "1") (pinfunction "C_1") (pintype "passive"))
      (node (ref "R10") (pin "2") (pinfunction "2_2") (pintype "passive"))
      (node (ref "R2") (pin "2") (pinfunction "2_2") (pintype "passive"))
      (node (ref "U3") (pin "1") (pinfunction "~{RST}_1") (pintype "passive"))
    )
    (net (code "66") (name "GND") (class "Default")
      (node (ref "*") (pin "1") (pinfunction "GND_1") (pintype "passive"))
      (node (ref "*1") (pin "23") (pinfunction "VSS_1_23") (pintype "passive"))
      (node (ref "*1") (pin "35") (pinfunction "VSS_2_35") (pintype "passive"))
      (node (ref "*1") (pin "47") (pinfunction "VSS_3_47") (pintype "passive"))
      (node (ref "*1") (pin "8") (pinfunction "VSSA_8") (pintype "passive"))
      (node (ref "C10") (pin "2") (pinfunction "2_2") (pintype "passive"))
      (node (ref "C11") (pin "2") (pinfunction "2_2") (pintype "passive"))
      (node (ref "C12") (pin "2") (pinfunction "2_2") (pintype "passive"))
      (node (ref "C13") (pin "1") (pinfunction "1_1") (pintype "passive"))
      (node (ref "C14") (pin "1") (pinfunction "1_1") (pintype "passive"))
      (node (ref "C15") (pin "1") (pinfunction "1_1") (pintype "passive"))
      (node (ref "C16") (pin "1") (pinfunction "1_1") (pintype "passive"))
      (node (ref "C17") (pin "1") (pinfunction "1_1") (pintype "passive"))
      (node (ref "C18") (pin "1") (pinfunction "1_1") (pintype "passive"))
      (node (ref "C2") (pin "1") (pinfunction "1_1") (pintype "passive"))
      (node (ref "C3") (pin "2") (pinfunction "2_2") (pintype "passive"))
      (node (ref "C4") (pin "1") (pinfunction "1_1") (pintype "passive"))
      (node (ref "C6") (pin "1") (pinfunction "1_1") (pintype "passive"))
      (node (ref "C7") (pin "1") (pinfunction "1_1") (pintype "passive"))
      (node (ref "C8") (pin "1") (pinfunction "1_1") (pintype "passive"))
      (node (ref "C9") (pin "2") (pinfunction "2_2") (pintype "passive"))
      (node (ref "P1") (pin "1") (pinfunction "1_1") (pintype "passive"))
      (node (ref "P1") (pin "2") (pinfunction "2_2") (pintype "passive"))
      (node (ref "P11") (pin "1") (pinfunction "1_1") (pintype "passive"))
      (node (ref "P12") (pin "3") (pinfunction "3_3") (pintype "passive"))
      (node (ref "P12") (pin "7") (pinfunction "7_7") (pintype "passive"))
      (node (ref "P13") (pin "5") (pinfunction "5_5") (pintype "passive"))
      (node (ref "P13") (pin "6") (pinfunction "6_6") (pintype "passive"))
      (node (ref "P2") (pin "17") (pinfunction "17_17") (pintype "passive"))
      (node (ref "P3") (pin "5") (pinfunction "5_5") (pintype "passive"))
      (node (ref "P3") (pin "6") (pinfunction "6_6") (pintype "passive"))
      (node (ref "P5") (pin "7") (pinfunction "7_7") (pintype "passive"))
      (node (ref "P7") (pin "1") (pinfunction "1_1") (pintype "passive"))
      (node (ref "P8") (pin "1") (pinfunction "1_1") (pintype "passive"))
      (node (ref "P8") (pin "7") (pinfunction "7_7") (pintype "passive"))
      (node (ref "R1") (pin "1") (pinfunction "1_1") (pintype "passive"))
      (node (ref "R15") (pin "1") (pinfunction "1_1") (pintype "passive"))
      (node (ref "R20") (pin "2") (pinfunction "2_2") (pintype "passive"))
      (node (ref "R6") (pin "1") (pinfunction "1_1") (pintype "passive"))
      (node (ref "S1") (pin "2") (pinfunction "2_2") (pintype "passive"))
      (node (ref "S2") (pin "2") (pinfunction "2_2") (pintype "passive"))
      (node (ref "S3") (pin "1") (pinfunction "1_1") (pintype "passive"))
      (node (ref "S4") (pin "1") (pinfunction "1_1") (pintype "passive"))
      (node (ref "S6") (pin "2") (pinfunction "2_2") (pintype "passive"))
      (node (ref "U1") (pin "1") (pinfunction "GND/ADJ_1") (pintype "passive"))
      (node (ref "U3") (pin "15") (pinfunction "GND_15") (pintype "passive"))
    )
    (net (code "67") (name "Net-(*-R232)") (class "Default")
      (node (ref "*") (pin "15") (pinfunction "R232_15") (pintype "passive"))
      (node (ref "Q2") (pin "3") (pinfunction "E_3") (pintype "passive"))
      (node (ref "R21") (pin "1") (pinfunction "1_1") (pintype "passive"))
    )
    (net (code "68") (name "Net-(*-RI#)") (class "Default")
      (node (ref "*") (pin "11") (pinfunction "RI#_11") (pintype "passive"))
      (node (ref "Q1") (pin "3") (pinfunction "E_3") (pintype "passive"))
      (node (ref "R22") (pin "1") (pinfunction "1_1") (pintype "passive"))
    )
    (net (code "69") (name "Net-(*-UD+)") (class "Default")
      (node (ref "*") (pin "5") (pinfunction "UD+_5") (pintype "passive"))
      (node (ref "P1") (pin "3") (pinfunction "3_3") (pintype "passive"))
      (node (ref "P14") (pin "2") (pinfunction "2_2") (pintype "passive"))
    )
    (net (code "70") (name "Net-(*-UD-)") (class "Default")
      (node (ref "*") (pin "6") (pinfunction "UD-_6") (pintype "passive"))
      (node (ref "P1") (pin "4") (pinfunction "4_4") (pintype "passive"))
      (node (ref "P14") (pin "1") (pinfunction "1_1") (pintype "passive"))
    )
    (net (code "71") (name "Net-(*-V3.3)") (class "Default")
      (node (ref "*") (pin "4") (pinfunction "V3.3_4") (pintype "passive"))
      (node (ref "C3") (pin "1") (pinfunction "1_1") (pintype "passive"))
    )
    (net (code "72") (name "Net-(*-XI)") (class "Default")
      (node (ref "*") (pin "7") (pinfunction "XI_7") (pintype "passive"))
      (node (ref "C2") (pin "2") (pinfunction "2_2") (pintype "passive"))
      (node (ref "Y1") (pin "1") (pinfunction "OSC1_1") (pintype "passive"))
    )
    (net (code "73") (name "Net-(*-XO)") (class "Default")
      (node (ref "*") (pin "8") (pinfunction "XO_8") (pintype "passive"))
      (node (ref "C4") (pin "2") (pinfunction "2_2") (pintype "passive"))
      (node (ref "Y1") (pin "2") (pinfunction "OSC2_2") (pintype "passive"))
    )
    (net (code "74") (name "Net-(A-A)") (class "Default")
      (node (ref "A") (pin "1") (pinfunction "A_1") (pintype "passive"))
      (node (ref "R12") (pin "2") (pinfunction "2_2") (pintype "passive"))
    )
    (net (code "75") (name "Net-(B-A)") (class "Default")
      (node (ref "B") (pin "1") (pinfunction "A_1") (pintype "passive"))
      (node (ref "R13") (pin "2") (pinfunction "2_2") (pintype "passive"))
    )
    (net (code "76") (name "Net-(D3-A)") (class "Default")
      (node (ref "D3") (pin "1") (pinfunction "A_1") (pintype "passive"))
      (node (ref "R9") (pin "1") (pinfunction "1_1") (pintype "passive"))
    )
    (net (code "77") (name "Net-(D4-K)") (class "Default")
      (node (ref "D4") (pin "2") (pinfunction "K_2") (pintype "passive"))
      (node (ref "R20") (pin "1") (pinfunction "1_1") (pintype "passive"))
    )
    (net (code "78") (name "Net-(P13-Pad3)") (class "Default")
      (node (ref "P13") (pin "3") (pinfunction "3_3") (pintype "passive"))
      (node (ref "R16") (pin "2") (pinfunction "2_2") (pintype "passive"))
    )
    (net (code "79") (name "Net-(P13-Pad4)") (class "Default")
      (node (ref "P13") (pin "4") (pinfunction "4_4") (pintype "passive"))
      (node (ref "R19") (pin "1") (pinfunction "1_1") (pintype "passive"))
    )
    (net (code "80") (name "Net-(Q1-B)") (class "Default")
      (node (ref "Q1") (pin "2") (pinfunction "B_2") (pintype "passive"))
      (node (ref "R21") (pin "2") (pinfunction "2_2") (pintype "passive"))
    )
    (net (code "81") (name "Net-(Q2-B)") (class "Default")
      (node (ref "Q2") (pin "2") (pinfunction "B_2") (pintype "passive"))
      (node (ref "R22") (pin "2") (pinfunction "2_2") (pintype "passive"))
    )
    (net (code "82") (name "Net-(R10-Pad1)") (class "Default")
      (node (ref "R10") (pin "1") (pinfunction "1_1") (pintype "passive"))
      (node (ref "R8") (pin "1") (pinfunction "1_1") (pintype "passive"))
      (node (ref "S1") (pin "1") (pinfunction "1_1") (pintype "passive"))
    )
    (net (code "83") (name "Net-(R11-Pad1)") (class "Default")
      (node (ref "R11") (pin "1") (pinfunction "1_1") (pintype "passive"))
      (node (ref "S2") (pin "1") (pinfunction "1_1") (pintype "passive"))
    )
    (net (code "84") (name "VCC_3V3") (class "Default")
      (node (ref "*1") (pin "24") (pinfunction "VDD_1_24") (pintype "passive"))
      (node (ref "*1") (pin "36") (pinfunction "VDD_2_36") (pintype "passive"))
      (node (ref "*1") (pin "48") (pinfunction "VDD_3_48") (pintype "passive"))
      (node (ref "*1") (pin "9") (pinfunction "VDDA_9") (pintype "passive"))
      (node (ref "C10") (pin "1") (pinfunction "1_1") (pintype "passive"))
      (node (ref "C11") (pin "1") (pinfunction "1_1") (pintype "passive"))
      (node (ref "C13") (pin "2") (pinfunction "2_2") (pintype "passive"))
      (node (ref "C9") (pin "1") (pinfunction "1_1") (pintype "passive"))
      (node (ref "D4") (pin "1") (pinfunction "A_1") (pintype "passive"))
      (node (ref "P11") (pin "2") (pinfunction "2_2") (pintype "passive"))
      (node (ref "P13") (pin "1") (pinfunction "1_1") (pintype "passive"))
      (node (ref "P13") (pin "2") (pinfunction "2_2") (pintype "passive"))
      (node (ref "P3") (pin "3") (pinfunction "3_3") (pintype "passive"))
      (node (ref "P3") (pin "4") (pinfunction "4_4") (pintype "passive"))
      (node (ref "P7") (pin "2") (pinfunction "2_2") (pintype "passive"))
      (node (ref "P8") (pin "2") (pinfunction "2_2") (pintype "passive"))
      (node (ref "R12") (pin "1") (pinfunction "1_1") (pintype "passive"))
      (node (ref "R13") (pin "1") (pinfunction "1_1") (pintype "passive"))
      (node (ref "R14") (pin "1") (pinfunction "1_1") (pintype "passive"))
      (node (ref "R17") (pin "1") (pinfunction "1_1") (pintype "passive"))
      (node (ref "R2") (pin "1") (pinfunction "1_1") (pintype "passive"))
      (node (ref "R3") (pin "1") (pinfunction "1_1") (pintype "passive"))
      (node (ref "R4") (pin "1") (pinfunction "1_1") (pintype "passive"))
      (node (ref "R5") (pin "1") (pinfunction "1_1") (pintype "passive"))
      (node (ref "R9") (pin "2") (pinfunction "2_2") (pintype "passive"))
      (node (ref "S5") (pin "1") (pinfunction "1_1") (pintype "passive"))
      (node (ref "U1") (pin "2") (pinfunction "VOUT_2") (pintype "passive"))
      (node (ref "U3") (pin "8") (pinfunction "VDD_8") (pintype "passive"))
    )
    (net (code "85") (name "VCC_5V") (class "Default")
      (node (ref "*") (pin "16") (pinfunction "VCC_16") (pintype "passive"))
      (node (ref "C6") (pin "2") (pinfunction "2_2") (pintype "passive"))
      (node (ref "C7") (pin "2") (pinfunction "2_2") (pintype "passive"))
      (node (ref "C8") (pin "2") (pinfunction "2_2") (pintype "passive"))
      (node (ref "D5") (pin "2") (pinfunction "K_2") (pintype "passive"))
      (node (ref "P12") (pin "4") (pinfunction "4_4") (pintype "passive"))
      (node (ref "P12") (pin "8") (pinfunction "8_8") (pintype "passive"))
      (node (ref "P3") (pin "1") (pinfunction "1_1") (pintype "passive"))
      (node (ref "P3") (pin "2") (pinfunction "2_2") (pintype "passive"))
      (node (ref "U1") (pin "3") (pinfunction "VIN_3") (pintype "passive"))
    )
    (net (code "86") (name "VCC_USB") (class "Default")
      (node (ref "D5") (pin "1") (pinfunction "A_1") (pintype "passive"))
      (node (ref "P1") (pin "5") (pinfunction "5_5") (pintype "passive"))
    )
    (net (code "87") (name "unconnected-(*-CTS#-Pad9)") (class "Default")
      (node (ref "*") (pin "9") (pinfunction "CTS#_9") (pintype "passive"))
    )
    (net (code "88") (name "unconnected-(*-DCD#-Pad12)") (class "Default")
      (node (ref "*") (pin "12") (pinfunction "DCD#_12") (pintype "passive"))
    )
    (net (code "89") (name "unconnected-(*-DSR#-Pad10)") (class "Default")
      (node (ref "*") (pin "10") (pinfunction "DSR#_10") (pintype "passive"))
    )
    (net (code "90") (name "unconnected-(*-DTR#-Pad13)") (class "Default")
      (node (ref "*") (pin "13") (pinfunction "DTR#_13") (pintype "passive"))
    )
    (net (code "91") (name "unconnected-(*-RTS#-Pad14)") (class "Default")
      (node (ref "*") (pin "14") (pinfunction "RTS#_14") (pintype "passive"))
    )
  )
)
